# fan7385_breakout.net
KiCad netlist of a schematic drawn in EAGLE
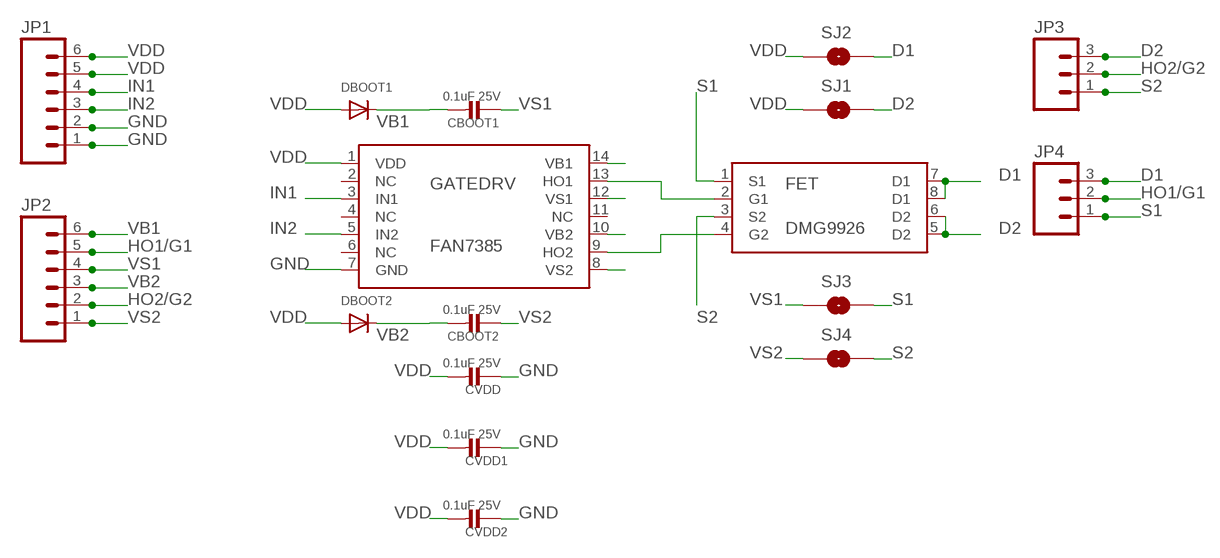
[diagram p0: schematic, sheet 1]

(export (version "E")
  (design (tool "Eeschema 10.0.6"))
  (components
    (comp (ref "CBOOT1")
      (value "0.1uF 25V")
      (footprint "eagle-import:0805")
      (libsource (lib "eagle-import") (part "CAP_CERAMIC0805"))
    )
    (comp (ref "CBOOT2")
      (value "0.1uF 25V")
      (footprint "eagle-import:0805")
      (libsource (lib "eagle-import") (part "CAP_CERAMIC0805"))
    )
    (comp (ref "CVDD")
      (value "0.1uF 25V")
      (footprint "eagle-import:0805")
      (libsource (lib "eagle-import") (part "CAP_CERAMIC0805"))
    )
    (comp (ref "CVDD1")
      (value "0.1uF 25V")
      (footprint "eagle-import:0805")
      (libsource (lib "eagle-import") (part "CAP_CERAMIC0805"))
    )
    (comp (ref "CVDD2")
      (value "0.1uF 25V")
      (footprint "eagle-import:0805")
      (libsource (lib "eagle-import") (part "CAP_CERAMIC0805"))
    )
    (comp (ref "DBOOT1")
      (value "DIODESOT23_WIDE")
      (footprint "eagle-import:SOT23-WIDE")
      (libsource (lib "eagle-import") (part "DIODESOT23_WIDE"))
    )
    (comp (ref "DBOOT2")
      (value "DIODESOT23_WIDE")
      (footprint "eagle-import:SOT23-WIDE")
      (libsource (lib "eagle-import") (part "DIODESOT23_WIDE"))
    )
    (comp (ref "FET")
      (value "DMG9926")
      (footprint "eagle-import:SOP8-L")
      (libsource (lib "eagle-import") (part "DMG9926"))
    )
    (comp (ref "GATEDRV")
      (value "FAN7385")
      (footprint "eagle-import:SOT14")
      (libsource (lib "eagle-import") (part "FAN7385"))
    )
    (comp (ref "JP1")
      (value "M06SIP")
      (footprint "eagle-import:1X06")
      (libsource (lib "eagle-import") (part "M06SIP"))
    )
    (comp (ref "JP2")
      (value "M06SIP")
      (footprint "eagle-import:1X06")
      (libsource (lib "eagle-import") (part "M06SIP"))
    )
    (comp (ref "JP3")
      (value "M03PTH")
      (footprint "eagle-import:1X03")
      (libsource (lib "eagle-import") (part "M03PTH"))
    )
    (comp (ref "JP4")
      (value "M03PTH")
      (footprint "eagle-import:1X03")
      (libsource (lib "eagle-import") (part "M03PTH"))
    )
    (comp (ref "SJ1")
      (value "SOLDERJUMPERNO")
      (footprint "eagle-import:SJ_2S-NO")
      (libsource (lib "eagle-import") (part "SOLDERJUMPERNO"))
    )
    (comp (ref "SJ2")
      (value "SOLDERJUMPERNO")
      (footprint "eagle-import:SJ_2S-NO")
      (libsource (lib "eagle-import") (part "SOLDERJUMPERNO"))
    )
    (comp (ref "SJ3")
      (value "SOLDERJUMPERTRACE")
      (footprint "eagle-import:SJ_2S-TRACE")
      (libsource (lib "eagle-import") (part "SOLDERJUMPERTRACE"))
    )
    (comp (ref "SJ4")
      (value "SOLDERJUMPERTRACE")
      (footprint "eagle-import:SJ_2S-TRACE")
      (libsource (lib "eagle-import") (part "SOLDERJUMPERTRACE"))
    )
  )
  (nets
    (net (code "1") (name "/D1") (class "Default")
      (node (ref "FET") (pin "7") (pinfunction "D1_7") (pintype "output"))
      (node (ref "FET") (pin "8") (pinfunction "D1_8") (pintype "output"))
      (node (ref "JP4") (pin "3") (pinfunction "3_3") (pintype "passive"))
      (node (ref "SJ2") (pin "2") (pinfunction "2_2") (pintype "passive"))
    )
    (net (code "2") (name "/D2") (class "Default")
      (node (ref "FET") (pin "5") (pinfunction "D2_5") (pintype "output"))
      (node (ref "FET") (pin "6") (pinfunction "D2_6") (pintype "output"))
      (node (ref "JP3") (pin "3") (pinfunction "3_3") (pintype "passive"))
      (node (ref "SJ1") (pin "2") (pinfunction "2_2") (pintype "passive"))
    )
    (net (code "3") (name "/GND") (class "Default")
      (node (ref "CVDD") (pin "1") (pinfunction "P$1_1") (pintype "passive"))
      (node (ref "CVDD1") (pin "1") (pinfunction "P$1_1") (pintype "passive"))
      (node (ref "CVDD2") (pin "1") (pinfunction "P$1_1") (pintype "passive"))
      (node (ref "GATEDRV") (pin "7") (pinfunction "GND_7") (pintype "power_in"))
      (node (ref "JP1") (pin "1") (pinfunction "1_1") (pintype "passive"))
      (node (ref "JP1") (pin "2") (pinfunction "2_2") (pintype "passive"))
    )
    (net (code "4") (name "/HO1{slash}G1") (class "Default")
      (node (ref "FET") (pin "2") (pinfunction "G1_2") (pintype "input"))
      (node (ref "GATEDRV") (pin "13") (pinfunction "HO1_13") (pintype "output"))
      (node (ref "JP2") (pin "5") (pinfunction "5_5") (pintype "passive"))
      (node (ref "JP4") (pin "2") (pinfunction "2_2") (pintype "passive"))
    )
    (net (code "5") (name "/HO2{slash}G2") (class "Default")
      (node (ref "FET") (pin "4") (pinfunction "G2_4") (pintype "input"))
      (node (ref "GATEDRV") (pin "9") (pinfunction "HO2_9") (pintype "output"))
      (node (ref "JP2") (pin "2") (pinfunction "2_2") (pintype "passive"))
      (node (ref "JP3") (pin "2") (pinfunction "2_2") (pintype "passive"))
    )
    (net (code "6") (name "/IN1") (class "Default")
      (node (ref "GATEDRV") (pin "3") (pinfunction "IN1_3") (pintype "input"))
      (node (ref "JP1") (pin "4") (pinfunction "4_4") (pintype "passive"))
    )
    (net (code "7") (name "/IN2") (class "Default")
      (node (ref "GATEDRV") (pin "5") (pinfunction "IN2_5") (pintype "input"))
      (node (ref "JP1") (pin "3") (pinfunction "3_3") (pintype "passive"))
    )
    (net (code "8") (name "/S1") (class "Default")
      (node (ref "FET") (pin "1") (pinfunction "S1_1") (pintype "input"))
      (node (ref "JP4") (pin "1") (pinfunction "1_1") (pintype "passive"))
      (node (ref "SJ3") (pin "2") (pinfunction "2_2") (pintype "passive"))
    )
    (net (code "9") (name "/S2") (class "Default")
      (node (ref "FET") (pin "3") (pinfunction "S2_3") (pintype "input"))
      (node (ref "JP3") (pin "1") (pinfunction "1_1") (pintype "passive"))
      (node (ref "SJ4") (pin "2") (pinfunction "2_2") (pintype "passive"))
    )
    (net (code "10") (name "/VB1") (class "Default")
      (node (ref "CBOOT1") (pin "2") (pinfunction "P$2_2") (pintype "passive"))
      (node (ref "DBOOT1") (pin "3") (pinfunction "C_3") (pintype "passive"))
      (node (ref "GATEDRV") (pin "14") (pinfunction "VB1_14") (pintype "input"))
      (node (ref "JP2") (pin "6") (pinfunction "6_6") (pintype "passive"))
    )
    (net (code "11") (name "/VB2") (class "Default")
      (node (ref "CBOOT2") (pin "2") (pinfunction "P$2_2") (pintype "passive"))
      (node (ref "DBOOT2") (pin "3") (pinfunction "C_3") (pintype "passive"))
      (node (ref "GATEDRV") (pin "10") (pinfunction "VB2_10") (pintype "input"))
      (node (ref "JP2") (pin "3") (pinfunction "3_3") (pintype "passive"))
    )
    (net (code "12") (name "/VDD") (class "Default")
      (node (ref "CVDD") (pin "2") (pinfunction "P$2_2") (pintype "passive"))
      (node (ref "CVDD1") (pin "2") (pinfunction "P$2_2") (pintype "passive"))
      (node (ref "CVDD2") (pin "2") (pinfunction "P$2_2") (pintype "passive"))
      (node (ref "DBOOT1") (pin "1") (pinfunction "A_1") (pintype "passive"))
      (node (ref "DBOOT2") (pin "1") (pinfunction "A_1") (pintype "passive"))
      (node (ref "GATEDRV") (pin "1") (pinfunction "VDD_1") (pintype "power_in"))
      (node (ref "JP1") (pin "5") (pinfunction "5_5") (pintype "passive"))
      (node (ref "JP1") (pin "6") (pinfunction "6_6") (pintype "passive"))
      (node (ref "SJ1") (pin "1") (pinfunction "1_1") (pintype "passive"))
      (node (ref "SJ2") (pin "1") (pinfunction "1_1") (pintype "passive"))
    )
    (net (code "13") (name "/VS1") (class "Default")
      (node (ref "CBOOT1") (pin "1") (pinfunction "P$1_1") (pintype "passive"))
      (node (ref "GATEDRV") (pin "12") (pinfunction "VS1_12") (pintype "input"))
      (node (ref "JP2") (pin "4") (pinfunction "4_4") (pintype "passive"))
      (node (ref "SJ3") (pin "1") (pinfunction "1_1") (pintype "passive"))
    )
    (net (code "14") (name "/VS2") (class "Default")
      (node (ref "CBOOT2") (pin "1") (pinfunction "P$1_1") (pintype "passive"))
      (node (ref "GATEDRV") (pin "8") (pinfunction "VS2_8") (pintype "input"))
      (node (ref "JP2") (pin "1") (pinfunction "1_1") (pintype "passive"))
      (node (ref "SJ4") (pin "1") (pinfunction "1_1") (pintype "passive"))
    )
    (net (code "15") (name "unconnected-(GATEDRV-NC-Pad2)") (class "Default")
      (node (ref "GATEDRV") (pin "2") (pinfunction "NC_2") (pintype "no_connect"))
    )
    (net (code "16") (name "unconnected-(GATEDRV-NC-Pad4)") (class "Default")
      (node (ref "GATEDRV") (pin "4") (pinfunction "NC_4") (pintype "no_connect"))
    )
    (net (code "17") (name "unconnected-(GATEDRV-NC-Pad6)") (class "Default")
      (node (ref "GATEDRV") (pin "6") (pinfunction "NC_6") (pintype "no_connect"))
    )
    (net (code "18") (name "unconnected-(GATEDRV-NC-Pad11)") (class "Default")
      (node (ref "GATEDRV") (pin "11") (pinfunction "NC_11") (pintype "no_connect"))
    )
  )
)
